# Transceivers.net
KiCad netlist of a schematic drawn in Altium Designer
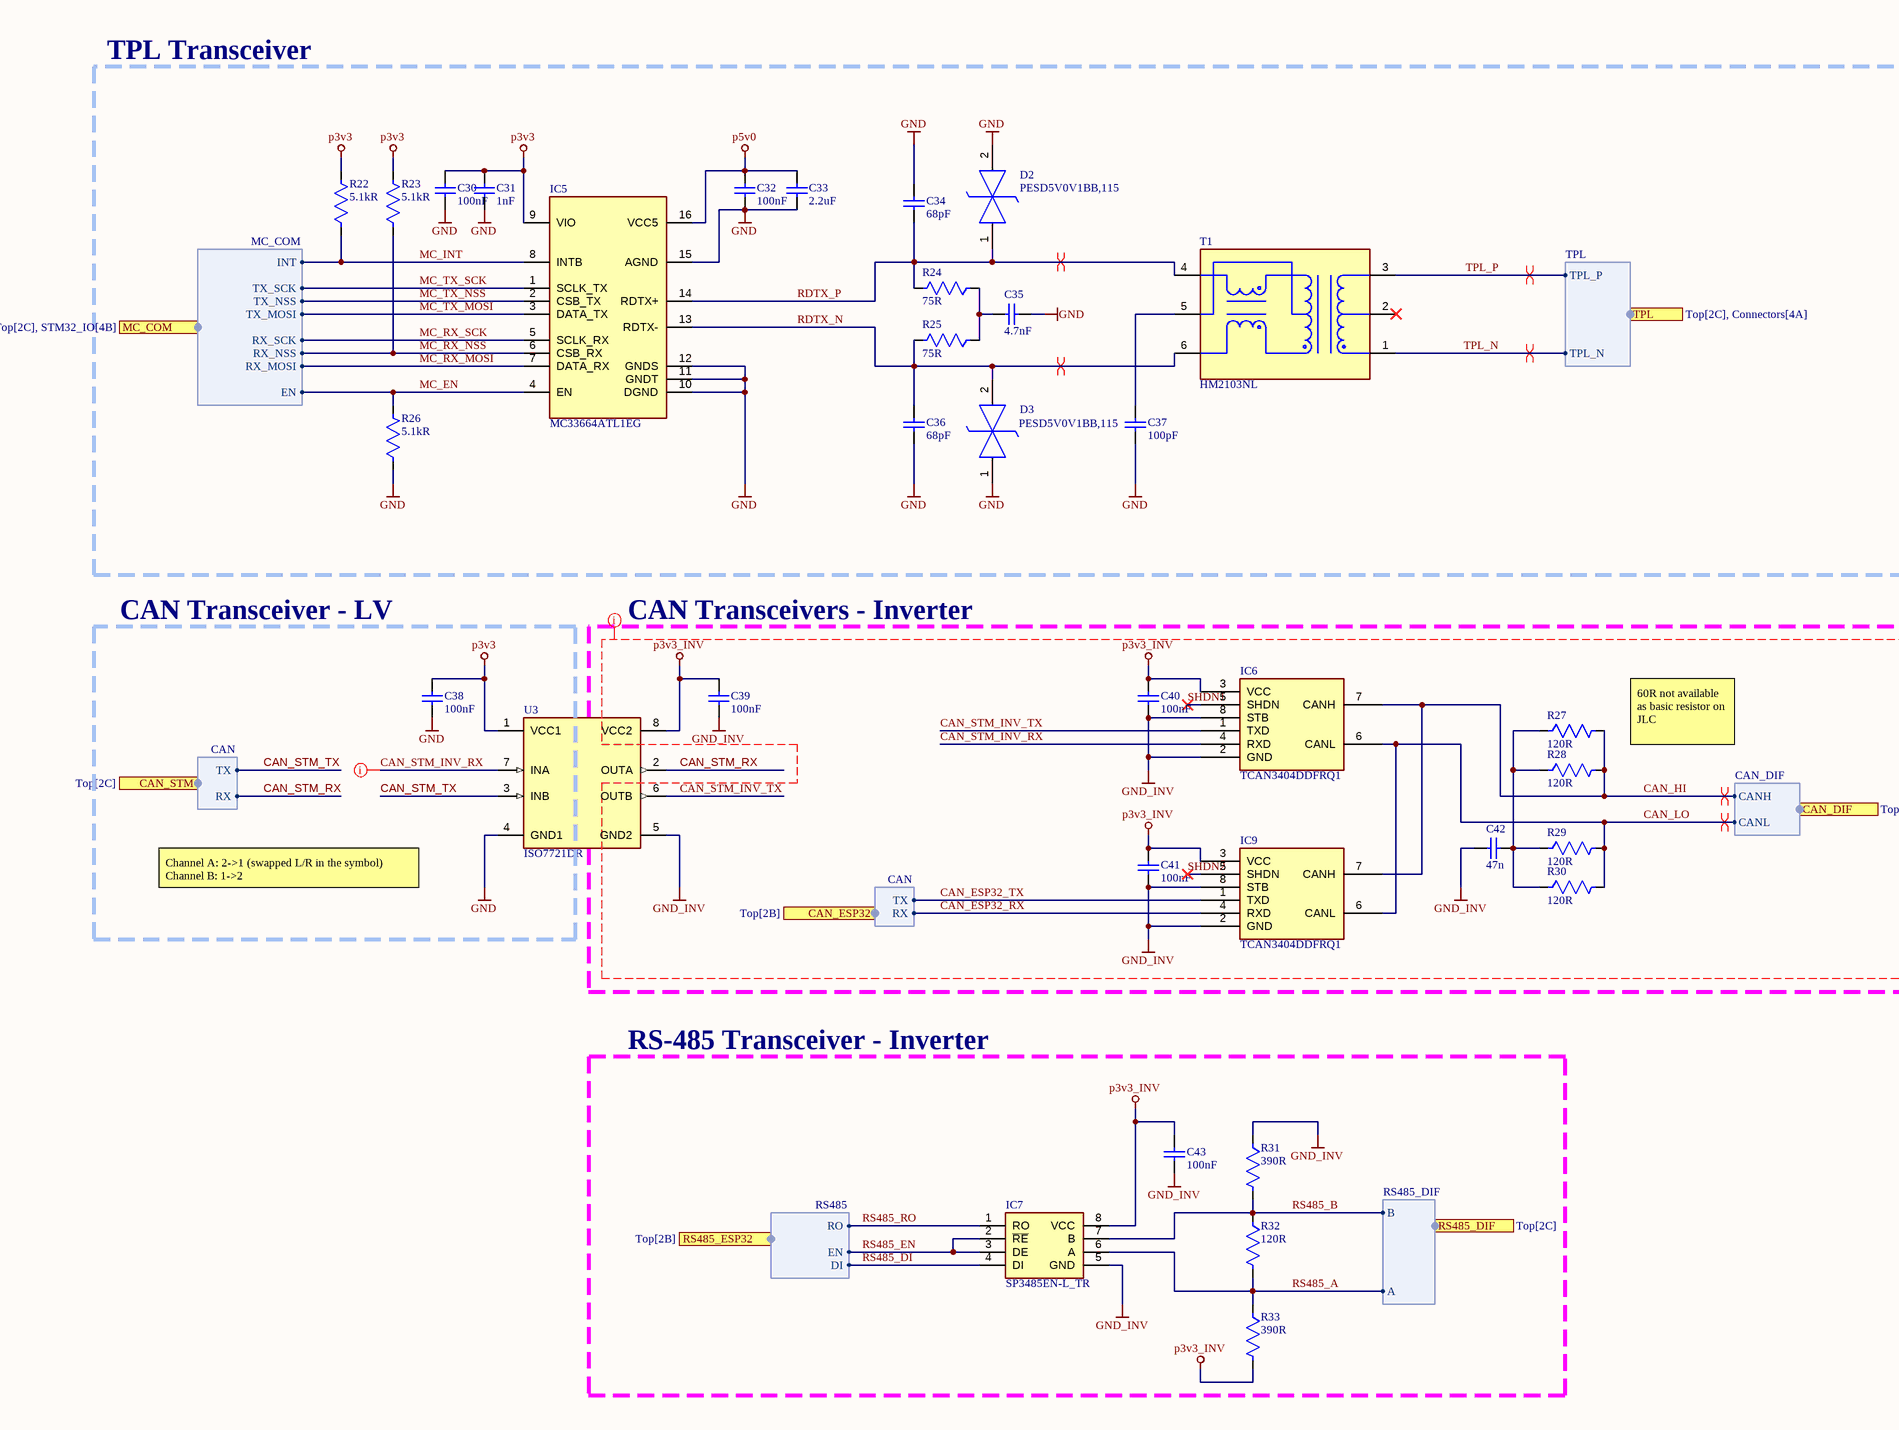
[diagram p0: Transceivers.SchDoc, left]
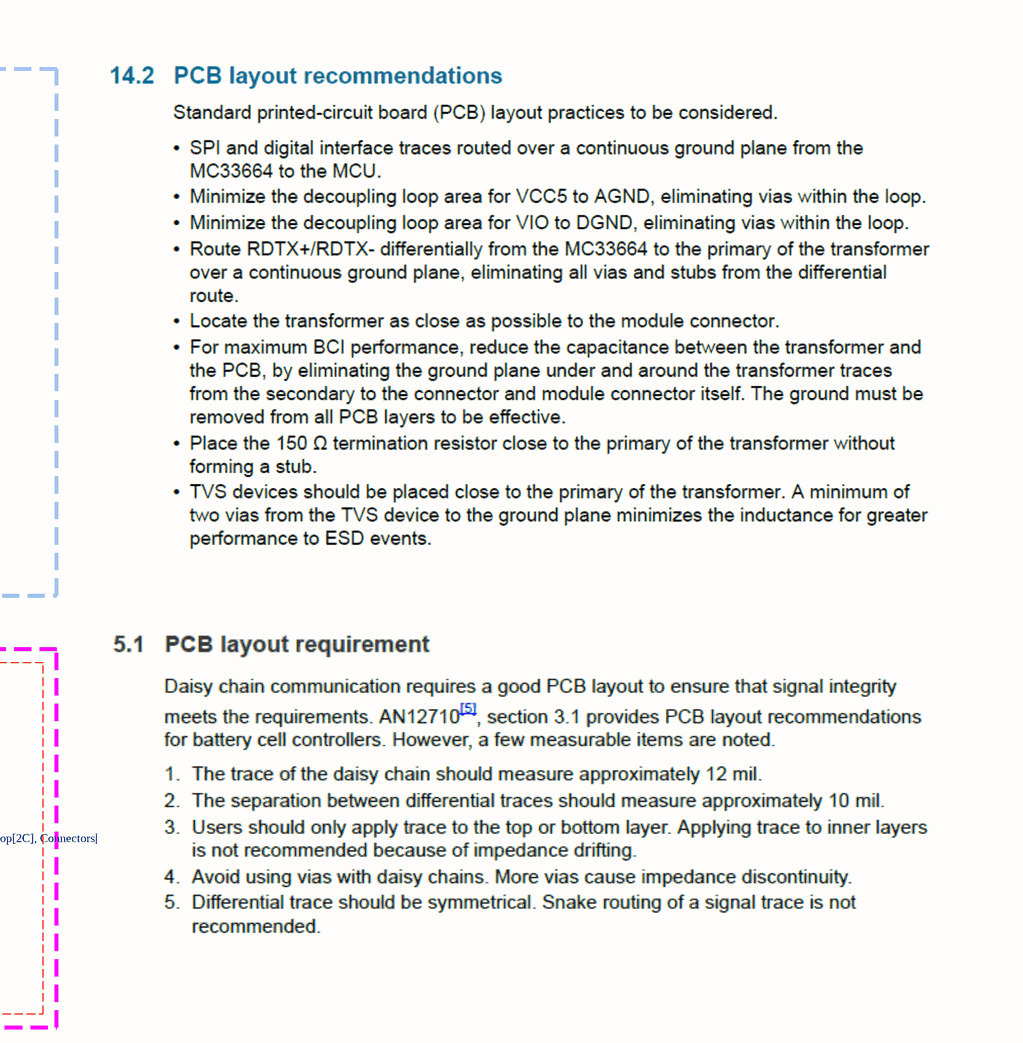
[diagram p1: Transceivers.SchDoc, right]

(export (version "E")
  (design (tool "Eeschema 10.0.6"))
  (components
    (comp (ref "C30")
      (value "100nF")
      (footprint "WCAP-CSGP_0402_L1W0.5H0.5")
      (description "GTT Standard 0402 non-polarized capacitor")
      (fields (field (name "JLCPCB PART #") "C1525") (field (name "Comment") "CAP 0402 100nF X7R"))
      (libsource (lib "Green Team Twente") (part "CAP_NONPOL_GENERIC"))
    )
    (comp (ref "C31")
      (value "1nF")
      (footprint "WCAP-CSGP_0402_L1W0.5H0.5")
      (description "GTT Standard 0402 non-polarized capacitor")
      (fields (field (name "JLCPCB PART #") "C1523") (field (name "Comment") "CAP 0402 1nF X7R"))
      (libsource (lib "Green Team Twente") (part "CAP_NONPOL_GENERIC"))
    )
    (comp (ref "C32")
      (value "100nF")
      (footprint "WCAP-CSGP_0402_L1W0.5H0.5")
      (description "GTT Standard 0402 non-polarized capacitor")
      (fields (field (name "JLCPCB PART #") "C1525") (field (name "Comment") "CAP 0402 100nF X7R"))
      (libsource (lib "Green Team Twente") (part "CAP_NONPOL_GENERIC"))
    )
    (comp (ref "C33")
      (value "2.2uF")
      (footprint "WCAP-CSGP_0603_L1.6W0.8H0.8_Reflow")
      (description "GTT Standard 0603 non-polarized capacitor")
      (fields (field (name "JLCPCB PART #") "C23630") (field (name "Comment") "CAP 0603 2.2uF X7R"))
      (libsource (lib "Green Team Twente") (part "CAP_NONPOL_GENERIC"))
    )
    (comp (ref "C34")
      (value "68pF")
      (footprint "WCAP-CSGP_0402_L1W0.5H0.5")
      (description "GTT Standard 0402 non-polarized capacitor")
      (fields (field (name "JLCPCB PART #") "C190580") (field (name "Comment") "CAP 0402 68pF X7R"))
      (libsource (lib "Green Team Twente") (part "CAP_NONPOL_GENERIC"))
    )
    (comp (ref "C35")
      (value "4.7nF")
      (footprint "WCAP-CSGP_0402_L1W0.5H0.5")
      (description "GTT Standard 0402 non-polarized capacitor")
      (fields (field (name "JLCPCB PART #") "C1538") (field (name "Comment") "CAP 0402 4.7nF X7R"))
      (libsource (lib "Green Team Twente") (part "CAP_NONPOL_GENERIC"))
    )
    (comp (ref "C36")
      (value "68pF")
      (footprint "WCAP-CSGP_0402_L1W0.5H0.5")
      (description "GTT Standard 0402 non-polarized capacitor")
      (fields (field (name "JLCPCB PART #") "C190580") (field (name "Comment") "CAP 0402 68pF X7R"))
      (libsource (lib "Green Team Twente") (part "CAP_NONPOL_GENERIC"))
    )
    (comp (ref "C37")
      (value "100pF")
      (footprint "WCAP-CSGP_0402_L1W0.5H0.5")
      (description "GTT Standard 0402 non-polarized capacitor")
      (fields (field (name "JLCPCB PART #") "C1546") (field (name "Comment") "CAP 0402 100pF X7R"))
      (libsource (lib "Green Team Twente") (part "CAP_NONPOL_GENERIC"))
    )
    (comp (ref "C38")
      (value "100nF")
      (footprint "WCAP-CSGP_0402_L1W0.5H0.5")
      (description "GTT Standard 0402 non-polarized capacitor")
      (fields (field (name "JLCPCB PART #") "C1525") (field (name "Comment") "CAP 0402 100nF X7R"))
      (libsource (lib "Green Team Twente") (part "CAP_NONPOL_GENERIC"))
    )
    (comp (ref "C39")
      (value "100nF")
      (footprint "WCAP-CSGP_0402_L1W0.5H0.5")
      (description "GTT Standard 0402 non-polarized capacitor")
      (fields (field (name "JLCPCB PART #") "C1525") (field (name "Comment") "CAP 0402 100nF X7R"))
      (libsource (lib "Green Team Twente") (part "CAP_NONPOL_GENERIC"))
    )
    (comp (ref "C40")
      (value "100nF")
      (footprint "WCAP-CSGP_0402_L1W0.5H0.5")
      (description "GTT Standard 0402 non-polarized capacitor")
      (fields (field (name "JLCPCB PART #") "C1525") (field (name "Comment") "CAP 0402 100nF X7R"))
      (libsource (lib "Green Team Twente") (part "CAP_NONPOL_GENERIC"))
    )
    (comp (ref "C41")
      (value "100nF")
      (footprint "WCAP-CSGP_0402_L1W0.5H0.5")
      (description "GTT Standard 0402 non-polarized capacitor")
      (fields (field (name "JLCPCB PART #") "C1525") (field (name "Comment") "CAP 0402 100nF X7R"))
      (libsource (lib "Green Team Twente") (part "CAP_NONPOL_GENERIC"))
    )
    (comp (ref "C42")
      (value "47n")
      (footprint "WCAP-CSGP_0603_L1.6W0.8H0.8_Reflow")
      (description "GTT Standard 0603 non-polarized capacitor")
      (fields (field (name "JLCPCB PART #") "C1622") (field (name "Comment") "CAP 0603 47n X7R"))
      (libsource (lib "Green Team Twente") (part "CAP_NONPOL_GENERIC"))
    )
    (comp (ref "C43")
      (value "100nF")
      (footprint "WCAP-CSGP_0402_L1W0.5H0.5")
      (description "GTT Standard 0402 non-polarized capacitor")
      (fields (field (name "JLCPCB PART #") "C1525") (field (name "Comment") "CAP 0402 100nF X7R"))
      (libsource (lib "Green Team Twente") (part "CAP_NONPOL_GENERIC"))
    )
    (comp (ref "D2")
      (value "PESD5V0V1BB,115")
      (footprint "PESD5V0V1BB115")
      (description "PESD5V0V1BB - Very low capacitance bidirectional ESD protection diode")
      (fields (field (name "MOUSER PART NUMBER") "771-PESD5V0V1BB115"))
      (libsource (lib "Green Team Twente") (part "PESD5V0V1BB,115"))
    )
    (comp (ref "D3")
      (value "PESD5V0V1BB,115")
      (footprint "PESD5V0V1BB115")
      (description "PESD5V0V1BB - Very low capacitance bidirectional ESD protection diode")
      (fields (field (name "MOUSER PART NUMBER") "771-PESD5V0V1BB115"))
      (libsource (lib "Green Team Twente") (part "PESD5V0V1BB,115"))
    )
    (comp (ref "IC5")
      (value "MC33664ATL1EG")
      (footprint "SOIC127P600X175-16N")
      (description "Interface - Specialized Isolated network high speed transceiver")
      (fields (field (name "MOUSER PART NUMBER") "841-MC33664ATL1EG"))
      (libsource (lib "Green Team Twente") (part "MC33664ATL1EG"))
    )
    (comp (ref "IC6")
      (value "TCAN3404DDFRQ1")
      (footprint "TSOT-23-8")
      (description "Integrated Circuit")
      (fields (field (name "JLCPCB PART #") "C32428067"))
      (libsource (lib "FlexBMS_lib") (part "TCAN3404DDFRQ1"))
    )
    (comp (ref "IC7")
      (value "SP3485EN-L_TR")
      (footprint "SOIC127P600X175-8N")
      (description "Integrated Circuit")
      (fields
        (field (name "MANUFACTURER_PART_NUMBER") "SP3485EN-L/TR")
        (field (name "MOUSER PART NUMBER") "701-SP3485EN-L/TR")
      )
      (libsource (lib "FlexBMS_lib") (part "SP3485EN-L_TR"))
    )
    (comp (ref "IC9")
      (value "TCAN3404DDFRQ1")
      (footprint "TSOT-23-8")
      (description "Integrated Circuit")
      (fields (field (name "JLCPCB PART #") "C32428067"))
      (libsource (lib "FlexBMS_lib") (part "TCAN3404DDFRQ1"))
    )
    (comp (ref "R22")
      (value "5.1kR")
      (footprint "FP0402")
      (description "GTT Standard 0402 Resistor")
      (fields (field (name "TOLERANCE") "1%") (field (name "POWER") "62.5mW"))
      (libsource (lib "Green Team Twente") (part "RES_GENERIC"))
    )
    (comp (ref "R23")
      (value "5.1kR")
      (footprint "FP0402")
      (description "GTT Standard 0402 Resistor")
      (fields (field (name "TOLERANCE") "1%") (field (name "POWER") "62.5mW"))
      (libsource (lib "Green Team Twente") (part "RES_GENERIC"))
    )
    (comp (ref "R24")
      (value "75R")
      (footprint "RES_SM0603_YAGEORC_N")
      (description "GTT Standard 0603 Resistor")
      (fields (field (name "POWER") "62.5mW") (field (name "TOLERANCE") "1%"))
      (libsource (lib "Green Team Twente") (part "RES_GENERIC"))
    )
    (comp (ref "R25")
      (value "75R")
      (footprint "RES_SM0603_YAGEORC_N")
      (description "GTT Standard 0603 Resistor")
      (fields (field (name "POWER") "62.5mW") (field (name "TOLERANCE") "1%"))
      (libsource (lib "Green Team Twente") (part "RES_GENERIC"))
    )
    (comp (ref "R26")
      (value "5.1kR")
      (footprint "FP0402")
      (description "GTT Standard 0402 Resistor")
      (fields (field (name "TOLERANCE") "1%") (field (name "POWER") "62.5mW"))
      (libsource (lib "Green Team Twente") (part "RES_GENERIC"))
    )
    (comp (ref "R27")
      (value "120R")
      (footprint "RES_SM0603_YAGEORC_N")
      (description "GTT Standard 0603 Resistor")
      (fields (field (name "POWER") "62.5mW") (field (name "TOLERANCE") "1%"))
      (libsource (lib "Green Team Twente") (part "RES_GENERIC"))
    )
    (comp (ref "R28")
      (value "120R")
      (footprint "RES_SM0603_YAGEORC_N")
      (description "GTT Standard 0603 Resistor")
      (fields (field (name "POWER") "62.5mW") (field (name "TOLERANCE") "1%"))
      (libsource (lib "Green Team Twente") (part "RES_GENERIC"))
    )
    (comp (ref "R29")
      (value "120R")
      (footprint "RES_SM0603_YAGEORC_N")
      (description "GTT Standard 0603 Resistor")
      (fields (field (name "POWER") "62.5mW") (field (name "TOLERANCE") "1%"))
      (libsource (lib "Green Team Twente") (part "RES_GENERIC"))
    )
    (comp (ref "R30")
      (value "120R")
      (footprint "RES_SM0603_YAGEORC_N")
      (description "GTT Standard 0603 Resistor")
      (fields (field (name "POWER") "62.5mW") (field (name "TOLERANCE") "1%"))
      (libsource (lib "Green Team Twente") (part "RES_GENERIC"))
    )
    (comp (ref "R31")
      (value "390R")
      (footprint "RES_SM0603_YAGEORC_N")
      (description "GTT Standard 0603 Resistor")
      (fields (field (name "POWER") "62.5mW") (field (name "TOLERANCE") "1%"))
      (libsource (lib "Green Team Twente") (part "RES_GENERIC"))
    )
    (comp (ref "R32")
      (value "120R")
      (footprint "RES_SM0603_YAGEORC_N")
      (description "GTT Standard 0603 Resistor")
      (fields (field (name "POWER") "62.5mW") (field (name "TOLERANCE") "1%"))
      (libsource (lib "Green Team Twente") (part "RES_GENERIC"))
    )
    (comp (ref "R33")
      (value "390R")
      (footprint "RES_SM0603_YAGEORC_N")
      (description "GTT Standard 0603 Resistor")
      (fields (field (name "POWER") "62.5mW") (field (name "TOLERANCE") "1%"))
      (libsource (lib "Green Team Twente") (part "RES_GENERIC"))
    )
    (comp (ref "T1")
      (value "HM2103NL")
      (footprint "FP-HM2103NL-MFG")
      (description "XFMR CMC MODULE AECQ BATT MNGT")
      (fields
        (field (name "OBSOLETE PART") "false")
        (field (name "OCTOPART") "https://octopart.com/hm2103nl-pulse-87646222")
      )
      (libsource (lib "Altium Content Vault") (part "8b1e087655f6b4593cc334a178269e5"))
    )
    (comp (ref "U3")
      (value "ISO7721DR")
      (footprint "FP-D0008B-MFG")
      (description "DGTL ISO 3KV GEN PRP 8SOIC")
      (libsource (lib "Altium Content Vault") (part "d04888473b947ce0c6c1d96650364e2"))
    )
  )
  (nets
    (net (code "7") (name "/CAN_ESP32_RX") (class "Default")
      (node (ref "IC9") (pin "4") (pinfunction "RXD_4") (pintype "passive"))
    )
    (net (code "8") (name "/CAN_ESP32_TX") (class "Default")
      (node (ref "IC9") (pin "1") (pinfunction "TXD_1") (pintype "passive"))
    )
    (net (code "9") (name "/CAN_HI") (class "Default")
      (node (ref "IC6") (pin "7") (pinfunction "CANH_7") (pintype "passive"))
      (node (ref "IC9") (pin "7") (pinfunction "CANH_7") (pintype "passive"))
      (node (ref "R27") (pin "2") (pinfunction "2_2") (pintype "passive"))
      (node (ref "R28") (pin "2") (pinfunction "2_2") (pintype "passive"))
    )
    (net (code "10") (name "/CAN_LO") (class "Default")
      (node (ref "IC6") (pin "6") (pinfunction "CANL_6") (pintype "passive"))
      (node (ref "IC9") (pin "6") (pinfunction "CANL_6") (pintype "passive"))
      (node (ref "R29") (pin "2") (pinfunction "2_2") (pintype "passive"))
      (node (ref "R30") (pin "2") (pinfunction "2_2") (pintype "passive"))
    )
    (net (code "11") (name "/CAN_STM_INV_RX") (class "Default")
      (node (ref "IC6") (pin "4") (pinfunction "RXD_4") (pintype "passive"))
      (node (ref "U3") (pin "7") (pinfunction "INA_7") (pintype "input"))
    )
    (net (code "12") (name "/CAN_STM_INV_TX") (class "Default")
      (node (ref "IC6") (pin "1") (pinfunction "TXD_1") (pintype "passive"))
      (node (ref "U3") (pin "6") (pinfunction "OUTB_6") (pintype "output"))
    )
    (net (code "13") (name "/CAN_STM_RX") (class "Default")
      (node (ref "U3") (pin "2") (pinfunction "OUTA_2") (pintype "output"))
    )
    (net (code "14") (name "/CAN_STM_TX") (class "Default")
      (node (ref "U3") (pin "3") (pinfunction "INB_3") (pintype "input"))
    )
    (net (code "15") (name "/MC_EN") (class "Default")
      (node (ref "IC5") (pin "4") (pinfunction "EN_4") (pintype "passive"))
      (node (ref "R26") (pin "2") (pinfunction "2_2") (pintype "passive"))
    )
    (net (code "16") (name "/MC_INT") (class "Default")
      (node (ref "IC5") (pin "8") (pinfunction "INTB_8") (pintype "passive"))
      (node (ref "R22") (pin "1") (pinfunction "1_1") (pintype "passive"))
    )
    (net (code "17") (name "/MC_RX_MOSI") (class "Default")
      (node (ref "IC5") (pin "7") (pinfunction "DATA_RX_7") (pintype "passive"))
    )
    (net (code "18") (name "/MC_RX_NSS") (class "Default")
      (node (ref "IC5") (pin "6") (pinfunction "CSB_RX_6") (pintype "passive"))
      (node (ref "R23") (pin "1") (pinfunction "1_1") (pintype "passive"))
    )
    (net (code "19") (name "/MC_RX_SCK") (class "Default")
      (node (ref "IC5") (pin "5") (pinfunction "SCLK_RX_5") (pintype "passive"))
    )
    (net (code "20") (name "/MC_TX_MOSI") (class "Default")
      (node (ref "IC5") (pin "3") (pinfunction "DATA_TX_3") (pintype "passive"))
    )
    (net (code "21") (name "/MC_TX_NSS") (class "Default")
      (node (ref "IC5") (pin "2") (pinfunction "CSB_TX_2") (pintype "passive"))
    )
    (net (code "22") (name "/MC_TX_SCK") (class "Default")
      (node (ref "IC5") (pin "1") (pinfunction "SCLK_TX_1") (pintype "passive"))
    )
    (net (code "23") (name "/RDTX_N") (class "Default")
      (node (ref "C36") (pin "2") (pinfunction "2_2") (pintype "passive"))
      (node (ref "D3") (pin "2") (pinfunction "K2_2") (pintype "passive"))
      (node (ref "IC5") (pin "13") (pinfunction "RDTX-_13") (pintype "passive"))
      (node (ref "R25") (pin "2") (pinfunction "2_2") (pintype "passive"))
      (node (ref "T1") (pin "6") (pinfunction "6_6") (pintype "passive"))
    )
    (net (code "24") (name "/RDTX_P") (class "Default")
      (node (ref "C34") (pin "1") (pinfunction "1_1") (pintype "passive"))
      (node (ref "D2") (pin "1") (pinfunction "K1_1") (pintype "passive"))
      (node (ref "IC5") (pin "14") (pinfunction "RDTX+_14") (pintype "passive"))
      (node (ref "R24") (pin "2") (pinfunction "2_2") (pintype "passive"))
      (node (ref "T1") (pin "4") (pinfunction "4_4") (pintype "passive"))
    )
    (net (code "25") (name "/RS485_A") (class "Default")
      (node (ref "IC7") (pin "6") (pinfunction "A_6") (pintype "passive"))
      (node (ref "R32") (pin "2") (pinfunction "2_2") (pintype "passive"))
      (node (ref "R33") (pin "1") (pinfunction "1_1") (pintype "passive"))
    )
    (net (code "26") (name "/RS485_B") (class "Default")
      (node (ref "IC7") (pin "7") (pinfunction "B_7") (pintype "passive"))
      (node (ref "R31") (pin "2") (pinfunction "2_2") (pintype "passive"))
      (node (ref "R32") (pin "1") (pinfunction "1_1") (pintype "passive"))
    )
    (net (code "27") (name "/RS485_DI") (class "Default")
      (node (ref "IC7") (pin "4") (pinfunction "DI_4") (pintype "passive"))
    )
    (net (code "28") (name "/RS485_EN") (class "Default")
      (node (ref "IC7") (pin "2") (pinfunction "~{RE}_2") (pintype "passive"))
      (node (ref "IC7") (pin "3") (pinfunction "DE_3") (pintype "passive"))
    )
    (net (code "29") (name "/RS485_RO") (class "Default")
      (node (ref "IC7") (pin "1") (pinfunction "RO_1") (pintype "passive"))
    )
    (net (code "30") (name "/SHDN1") (class "Default")
      (node (ref "IC6") (pin "5") (pinfunction "SHDN_5") (pintype "passive+no_connect"))
    )
    (net (code "31") (name "/SHDN2") (class "Default")
      (node (ref "IC9") (pin "5") (pinfunction "SHDN_5") (pintype "passive+no_connect"))
    )
    (net (code "32") (name "/TPL_N") (class "Default")
      (node (ref "T1") (pin "1") (pinfunction "1_1") (pintype "passive"))
    )
    (net (code "33") (name "/TPL_P") (class "Default")
      (node (ref "T1") (pin "3") (pinfunction "3_3") (pintype "passive"))
    )
    (net (code "40") (name "GND") (class "Default")
      (node (ref "C30") (pin "1") (pinfunction "1_1") (pintype "passive"))
      (node (ref "C31") (pin "1") (pinfunction "1_1") (pintype "passive"))
      (node (ref "C32") (pin "1") (pinfunction "1_1") (pintype "passive"))
      (node (ref "C33") (pin "1") (pinfunction "1_1") (pintype "passive"))
      (node (ref "C34") (pin "2") (pinfunction "2_2") (pintype "passive"))
      (node (ref "C35") (pin "1") (pinfunction "1_1") (pintype "passive"))
      (node (ref "C36") (pin "1") (pinfunction "1_1") (pintype "passive"))
      (node (ref "C37") (pin "1") (pinfunction "1_1") (pintype "passive"))
      (node (ref "C38") (pin "1") (pinfunction "1_1") (pintype "passive"))
      (node (ref "D2") (pin "2") (pinfunction "K2_2") (pintype "passive"))
      (node (ref "D3") (pin "1") (pinfunction "K1_1") (pintype "passive"))
      (node (ref "IC5") (pin "10") (pinfunction "DGND_10") (pintype "passive"))
      (node (ref "IC5") (pin "11") (pinfunction "GNDT_11") (pintype "passive"))
      (node (ref "IC5") (pin "12") (pinfunction "GNDS_12") (pintype "passive"))
      (node (ref "IC5") (pin "15") (pinfunction "AGND_15") (pintype "passive"))
      (node (ref "R26") (pin "1") (pinfunction "1_1") (pintype "passive"))
      (node (ref "U3") (pin "4") (pinfunction "GND1_4") (pintype "power_in"))
    )
    (net (code "41") (name "GND_INV") (class "Default")
      (node (ref "C39") (pin "1") (pinfunction "1_1") (pintype "passive"))
      (node (ref "C40") (pin "1") (pinfunction "1_1") (pintype "passive"))
      (node (ref "C41") (pin "1") (pinfunction "1_1") (pintype "passive"))
      (node (ref "C42") (pin "2") (pinfunction "2_2") (pintype "passive"))
      (node (ref "C43") (pin "1") (pinfunction "1_1") (pintype "passive"))
      (node (ref "IC6") (pin "2") (pinfunction "GND_2") (pintype "passive"))
      (node (ref "IC6") (pin "8") (pinfunction "STB_8") (pintype "passive"))
      (node (ref "IC7") (pin "5") (pinfunction "GND_5") (pintype "passive"))
      (node (ref "IC9") (pin "2") (pinfunction "GND_2") (pintype "passive"))
      (node (ref "IC9") (pin "8") (pinfunction "STB_8") (pintype "passive"))
      (node (ref "R31") (pin "1") (pinfunction "1_1") (pintype "passive"))
      (node (ref "U3") (pin "5") (pinfunction "GND2_5") (pintype "power_in"))
    )
    (net (code "42") (name "Net-(C35-Pad2)") (class "Default")
      (node (ref "C35") (pin "2") (pinfunction "2_2") (pintype "passive"))
      (node (ref "R24") (pin "1") (pinfunction "1_1") (pintype "passive"))
      (node (ref "R25") (pin "1") (pinfunction "1_1") (pintype "passive"))
    )
    (net (code "43") (name "Net-(C37-Pad2)") (class "Default")
      (node (ref "C37") (pin "2") (pinfunction "2_2") (pintype "passive"))
      (node (ref "T1") (pin "5") (pinfunction "5_5") (pintype "passive"))
    )
    (net (code "44") (name "Net-(C42-Pad1)") (class "Default")
      (node (ref "C42") (pin "1") (pinfunction "1_1") (pintype "passive"))
      (node (ref "R27") (pin "1") (pinfunction "1_1") (pintype "passive"))
      (node (ref "R28") (pin "1") (pinfunction "1_1") (pintype "passive"))
      (node (ref "R29") (pin "1") (pinfunction "1_1") (pintype "passive"))
      (node (ref "R30") (pin "1") (pinfunction "1_1") (pintype "passive"))
    )
    (net (code "45") (name "p3v3") (class "Default")
      (node (ref "C30") (pin "2") (pinfunction "2_2") (pintype "passive"))
      (node (ref "C31") (pin "2") (pinfunction "2_2") (pintype "passive"))
      (node (ref "C38") (pin "2") (pinfunction "2_2") (pintype "passive"))
      (node (ref "IC5") (pin "9") (pinfunction "VIO_9") (pintype "passive"))
      (node (ref "R22") (pin "2") (pinfunction "2_2") (pintype "passive"))
      (node (ref "R23") (pin "2") (pinfunction "2_2") (pintype "passive"))
      (node (ref "U3") (pin "1") (pinfunction "VCC1_1") (pintype "power_in"))
    )
    (net (code "46") (name "p3v3_INV") (class "Default")
      (node (ref "C39") (pin "2") (pinfunction "2_2") (pintype "passive"))
      (node (ref "C40") (pin "2") (pinfunction "2_2") (pintype "passive"))
      (node (ref "C41") (pin "2") (pinfunction "2_2") (pintype "passive"))
      (node (ref "C43") (pin "2") (pinfunction "2_2") (pintype "passive"))
      (node (ref "IC6") (pin "3") (pinfunction "VCC_3") (pintype "passive"))
      (node (ref "IC7") (pin "8") (pinfunction "VCC_8") (pintype "passive"))
      (node (ref "IC9") (pin "3") (pinfunction "VCC_3") (pintype "passive"))
      (node (ref "R33") (pin "2") (pinfunction "2_2") (pintype "passive"))
      (node (ref "U3") (pin "8") (pinfunction "VCC2_8") (pintype "power_in"))
    )
    (net (code "47") (name "p5v0") (class "Default")
      (node (ref "C32") (pin "2") (pinfunction "2_2") (pintype "passive"))
      (node (ref "C33") (pin "2") (pinfunction "2_2") (pintype "passive"))
      (node (ref "IC5") (pin "16") (pinfunction "VCC5_16") (pintype "passive"))
    )
    (net (code "48") (name "unconnected-(T1-Pad2)") (class "Default")
      (node (ref "T1") (pin "2") (pinfunction "2_2") (pintype "passive+no_connect"))
    )
  )
)
